# LC_BigOne_-_Comm_Connectors.net
KiCad netlist of a schematic drawn in Altium Designer
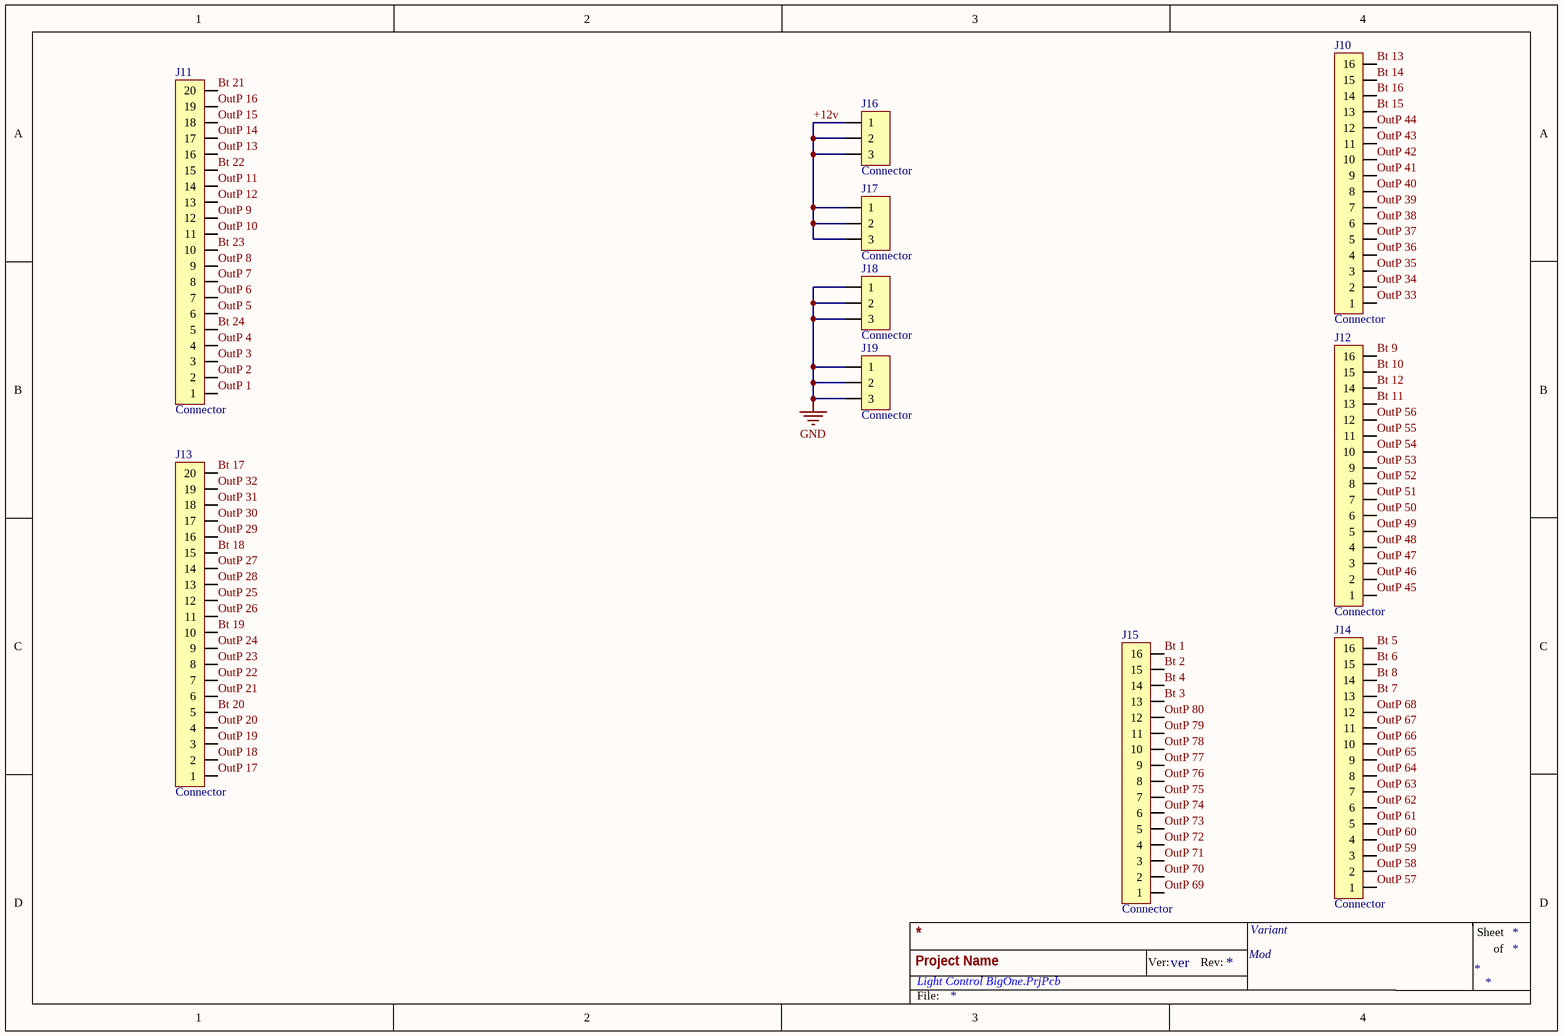
[diagram p0: LC BigOne - Comm Connectors.SchDoc]

(export (version "E")
  (design (tool "Eeschema 10.0.6"))
  (components
    (comp (ref "J10")
      (value "Connector")
      (footprint "Connector:LINE 2.54 x 16D (2 x 8) BH")
      (description "Vert, Dbl line, Male")
      (libsource (lib "Connector") (part "PLD-16 (2 x 8)"))
    )
    (comp (ref "J11")
      (value "Connector")
      (footprint "Connector:LINE 2.54 x 20D (2 x 10) - BH")
      (description "Vert, Dbl line, Male")
      (libsource (lib "Connector") (part "PLD-20 (2 x 10)"))
    )
    (comp (ref "J12")
      (value "Connector")
      (footprint "Connector:LINE 2.54 x 16D (2 x 8) BH")
      (description "Vert, Dbl line, Male")
      (libsource (lib "Connector") (part "PLD-16 (2 x 8)"))
    )
    (comp (ref "J13")
      (value "Connector")
      (footprint "Connector:LINE 2.54 x 20D (2 x 10) - BH")
      (description "Vert, Dbl line, Male")
      (libsource (lib "Connector") (part "PLD-20 (2 x 10)"))
    )
    (comp (ref "J14")
      (value "Connector")
      (footprint "Connector:LINE 2.54 x 16D (2 x 8) BH")
      (description "Vert, Dbl line, Male")
      (libsource (lib "Connector") (part "PLD-16 (2 x 8)"))
    )
    (comp (ref "J15")
      (value "Connector")
      (footprint "Connector:LINE 2.54 x 16D (2 x 8) BH")
      (description "Vert, Dbl line, Male")
      (libsource (lib "Connector") (part "PLD-16 (2 x 8)"))
    )
    (comp (ref "J16")
      (value "Connector")
      (footprint "Connector:DG301 5mm 3p")
      (description "DG301 series")
      (libsource (lib "Connector") (part "DG301-5.0-3P12"))
    )
    (comp (ref "J17")
      (value "Connector")
      (footprint "Connector:DG301 5mm 3p")
      (description "DG301 series")
      (libsource (lib "Connector") (part "DG301-5.0-3P12"))
    )
    (comp (ref "J18")
      (value "Connector")
      (footprint "Connector:DG301 5mm 3p")
      (description "DG301 series")
      (libsource (lib "Connector") (part "DG301-5.0-3P12"))
    )
    (comp (ref "J19")
      (value "Connector")
      (footprint "Connector:DG301 5mm 3p")
      (description "DG301 series")
      (libsource (lib "Connector") (part "DG301-5.0-3P12"))
    )
  )
  (nets
    (net (code "1") (name "/+12v") (class "Default")
      (node (ref "J16") (pin "1") (pinfunction "1_1") (pintype "passive"))
      (node (ref "J16") (pin "2") (pinfunction "2_2") (pintype "passive"))
      (node (ref "J16") (pin "3") (pinfunction "3_3") (pintype "passive"))
      (node (ref "J17") (pin "1") (pinfunction "1_1") (pintype "passive"))
      (node (ref "J17") (pin "2") (pinfunction "2_2") (pintype "passive"))
      (node (ref "J17") (pin "3") (pinfunction "3_3") (pintype "passive"))
    )
    (net (code "2") (name "/Bt 1") (class "Default")
      (node (ref "J15") (pin "16") (pinfunction "16_16") (pintype "passive"))
    )
    (net (code "3") (name "/Bt 2") (class "Default")
      (node (ref "J15") (pin "15") (pinfunction "15_15") (pintype "passive"))
    )
    (net (code "4") (name "/Bt 3") (class "Default")
      (node (ref "J15") (pin "13") (pinfunction "13_13") (pintype "passive"))
    )
    (net (code "5") (name "/Bt 4") (class "Default")
      (node (ref "J15") (pin "14") (pinfunction "14_14") (pintype "passive"))
    )
    (net (code "6") (name "/Bt 5") (class "Default")
      (node (ref "J14") (pin "16") (pinfunction "16_16") (pintype "passive"))
    )
    (net (code "7") (name "/Bt 6") (class "Default")
      (node (ref "J14") (pin "15") (pinfunction "15_15") (pintype "passive"))
    )
    (net (code "8") (name "/Bt 7") (class "Default")
      (node (ref "J14") (pin "13") (pinfunction "13_13") (pintype "passive"))
    )
    (net (code "9") (name "/Bt 8") (class "Default")
      (node (ref "J14") (pin "14") (pinfunction "14_14") (pintype "passive"))
    )
    (net (code "10") (name "/Bt 9") (class "Default")
      (node (ref "J12") (pin "16") (pinfunction "16_16") (pintype "passive"))
    )
    (net (code "11") (name "/Bt 10") (class "Default")
      (node (ref "J12") (pin "15") (pinfunction "15_15") (pintype "passive"))
    )
    (net (code "12") (name "/Bt 11") (class "Default")
      (node (ref "J12") (pin "13") (pinfunction "13_13") (pintype "passive"))
    )
    (net (code "13") (name "/Bt 12") (class "Default")
      (node (ref "J12") (pin "14") (pinfunction "14_14") (pintype "passive"))
    )
    (net (code "14") (name "/Bt 13") (class "Default")
      (node (ref "J10") (pin "16") (pinfunction "16_16") (pintype "passive"))
    )
    (net (code "15") (name "/Bt 14") (class "Default")
      (node (ref "J10") (pin "15") (pinfunction "15_15") (pintype "passive"))
    )
    (net (code "16") (name "/Bt 15") (class "Default")
      (node (ref "J10") (pin "13") (pinfunction "13_13") (pintype "passive"))
    )
    (net (code "17") (name "/Bt 16") (class "Default")
      (node (ref "J10") (pin "14") (pinfunction "14_14") (pintype "passive"))
    )
    (net (code "18") (name "/Bt 17") (class "Default")
      (node (ref "J13") (pin "20") (pinfunction "20_20") (pintype "passive"))
    )
    (net (code "19") (name "/Bt 18") (class "Default")
      (node (ref "J13") (pin "15") (pinfunction "15_15") (pintype "passive"))
    )
    (net (code "20") (name "/Bt 19") (class "Default")
      (node (ref "J13") (pin "10") (pinfunction "10_10") (pintype "passive"))
    )
    (net (code "21") (name "/Bt 20") (class "Default")
      (node (ref "J13") (pin "5") (pinfunction "5_5") (pintype "passive"))
    )
    (net (code "22") (name "/Bt 21") (class "Default")
      (node (ref "J11") (pin "20") (pinfunction "20_20") (pintype "passive"))
    )
    (net (code "23") (name "/Bt 22") (class "Default")
      (node (ref "J11") (pin "15") (pinfunction "15_15") (pintype "passive"))
    )
    (net (code "24") (name "/Bt 23") (class "Default")
      (node (ref "J11") (pin "10") (pinfunction "10_10") (pintype "passive"))
    )
    (net (code "25") (name "/Bt 24") (class "Default")
      (node (ref "J11") (pin "5") (pinfunction "5_5") (pintype "passive"))
    )
    (net (code "26") (name "/OutP 1") (class "Default")
      (node (ref "J11") (pin "1") (pinfunction "1_1") (pintype "passive"))
    )
    (net (code "27") (name "/OutP 2") (class "Default")
      (node (ref "J11") (pin "2") (pinfunction "2_2") (pintype "passive"))
    )
    (net (code "28") (name "/OutP 3") (class "Default")
      (node (ref "J11") (pin "3") (pinfunction "3_3") (pintype "passive"))
    )
    (net (code "29") (name "/OutP 4") (class "Default")
      (node (ref "J11") (pin "4") (pinfunction "4_4") (pintype "passive"))
    )
    (net (code "30") (name "/OutP 5") (class "Default")
      (node (ref "J11") (pin "6") (pinfunction "6_6") (pintype "passive"))
    )
    (net (code "31") (name "/OutP 6") (class "Default")
      (node (ref "J11") (pin "7") (pinfunction "7_7") (pintype "passive"))
    )
    (net (code "32") (name "/OutP 7") (class "Default")
      (node (ref "J11") (pin "8") (pinfunction "8_8") (pintype "passive"))
    )
    (net (code "33") (name "/OutP 8") (class "Default")
      (node (ref "J11") (pin "9") (pinfunction "9_9") (pintype "passive"))
    )
    (net (code "34") (name "/OutP 9") (class "Default")
      (node (ref "J11") (pin "12") (pinfunction "12_12") (pintype "passive"))
    )
    (net (code "35") (name "/OutP 10") (class "Default")
      (node (ref "J11") (pin "11") (pinfunction "11_11") (pintype "passive"))
    )
    (net (code "36") (name "/OutP 11") (class "Default")
      (node (ref "J11") (pin "14") (pinfunction "14_14") (pintype "passive"))
    )
    (net (code "37") (name "/OutP 12") (class "Default")
      (node (ref "J11") (pin "13") (pinfunction "13_13") (pintype "passive"))
    )
    (net (code "38") (name "/OutP 13") (class "Default")
      (node (ref "J11") (pin "16") (pinfunction "16_16") (pintype "passive"))
    )
    (net (code "39") (name "/OutP 14") (class "Default")
      (node (ref "J11") (pin "17") (pinfunction "17_17") (pintype "passive"))
    )
    (net (code "40") (name "/OutP 15") (class "Default")
      (node (ref "J11") (pin "18") (pinfunction "18_18") (pintype "passive"))
    )
    (net (code "41") (name "/OutP 16") (class "Default")
      (node (ref "J11") (pin "19") (pinfunction "19_19") (pintype "passive"))
    )
    (net (code "42") (name "/OutP 17") (class "Default")
      (node (ref "J13") (pin "1") (pinfunction "1_1") (pintype "passive"))
    )
    (net (code "43") (name "/OutP 18") (class "Default")
      (node (ref "J13") (pin "2") (pinfunction "2_2") (pintype "passive"))
    )
    (net (code "44") (name "/OutP 19") (class "Default")
      (node (ref "J13") (pin "3") (pinfunction "3_3") (pintype "passive"))
    )
    (net (code "45") (name "/OutP 20") (class "Default")
      (node (ref "J13") (pin "4") (pinfunction "4_4") (pintype "passive"))
    )
    (net (code "46") (name "/OutP 21") (class "Default")
      (node (ref "J13") (pin "6") (pinfunction "6_6") (pintype "passive"))
    )
    (net (code "47") (name "/OutP 22") (class "Default")
      (node (ref "J13") (pin "7") (pinfunction "7_7") (pintype "passive"))
    )
    (net (code "48") (name "/OutP 23") (class "Default")
      (node (ref "J13") (pin "8") (pinfunction "8_8") (pintype "passive"))
    )
    (net (code "49") (name "/OutP 24") (class "Default")
      (node (ref "J13") (pin "9") (pinfunction "9_9") (pintype "passive"))
    )
    (net (code "50") (name "/OutP 25") (class "Default")
      (node (ref "J13") (pin "12") (pinfunction "12_12") (pintype "passive"))
    )
    (net (code "51") (name "/OutP 26") (class "Default")
      (node (ref "J13") (pin "11") (pinfunction "11_11") (pintype "passive"))
    )
    (net (code "52") (name "/OutP 27") (class "Default")
      (node (ref "J13") (pin "14") (pinfunction "14_14") (pintype "passive"))
    )
    (net (code "53") (name "/OutP 28") (class "Default")
      (node (ref "J13") (pin "13") (pinfunction "13_13") (pintype "passive"))
    )
    (net (code "54") (name "/OutP 29") (class "Default")
      (node (ref "J13") (pin "16") (pinfunction "16_16") (pintype "passive"))
    )
    (net (code "55") (name "/OutP 30") (class "Default")
      (node (ref "J13") (pin "17") (pinfunction "17_17") (pintype "passive"))
    )
    (net (code "56") (name "/OutP 31") (class "Default")
      (node (ref "J13") (pin "18") (pinfunction "18_18") (pintype "passive"))
    )
    (net (code "57") (name "/OutP 32") (class "Default")
      (node (ref "J13") (pin "19") (pinfunction "19_19") (pintype "passive"))
    )
    (net (code "58") (name "/OutP 33") (class "Default")
      (node (ref "J10") (pin "1") (pinfunction "1_1") (pintype "passive"))
    )
    (net (code "59") (name "/OutP 34") (class "Default")
      (node (ref "J10") (pin "2") (pinfunction "2_2") (pintype "passive"))
    )
    (net (code "60") (name "/OutP 35") (class "Default")
      (node (ref "J10") (pin "3") (pinfunction "3_3") (pintype "passive"))
    )
    (net (code "61") (name "/OutP 36") (class "Default")
      (node (ref "J10") (pin "4") (pinfunction "4_4") (pintype "passive"))
    )
    (net (code "62") (name "/OutP 37") (class "Default")
      (node (ref "J10") (pin "5") (pinfunction "5_5") (pintype "passive"))
    )
    (net (code "63") (name "/OutP 38") (class "Default")
      (node (ref "J10") (pin "6") (pinfunction "6_6") (pintype "passive"))
    )
    (net (code "64") (name "/OutP 39") (class "Default")
      (node (ref "J10") (pin "7") (pinfunction "7_7") (pintype "passive"))
    )
    (net (code "65") (name "/OutP 40") (class "Default")
      (node (ref "J10") (pin "8") (pinfunction "8_8") (pintype "passive"))
    )
    (net (code "66") (name "/OutP 41") (class "Default")
      (node (ref "J10") (pin "9") (pinfunction "9_9") (pintype "passive"))
    )
    (net (code "67") (name "/OutP 42") (class "Default")
      (node (ref "J10") (pin "10") (pinfunction "10_10") (pintype "passive"))
    )
    (net (code "68") (name "/OutP 43") (class "Default")
      (node (ref "J10") (pin "11") (pinfunction "11_11") (pintype "passive"))
    )
    (net (code "69") (name "/OutP 44") (class "Default")
      (node (ref "J10") (pin "12") (pinfunction "12_12") (pintype "passive"))
    )
    (net (code "70") (name "/OutP 45") (class "Default")
      (node (ref "J12") (pin "1") (pinfunction "1_1") (pintype "passive"))
    )
    (net (code "71") (name "/OutP 46") (class "Default")
      (node (ref "J12") (pin "2") (pinfunction "2_2") (pintype "passive"))
    )
    (net (code "72") (name "/OutP 47") (class "Default")
      (node (ref "J12") (pin "3") (pinfunction "3_3") (pintype "passive"))
    )
    (net (code "73") (name "/OutP 48") (class "Default")
      (node (ref "J12") (pin "4") (pinfunction "4_4") (pintype "passive"))
    )
    (net (code "74") (name "/OutP 49") (class "Default")
      (node (ref "J12") (pin "5") (pinfunction "5_5") (pintype "passive"))
    )
    (net (code "75") (name "/OutP 50") (class "Default")
      (node (ref "J12") (pin "6") (pinfunction "6_6") (pintype "passive"))
    )
    (net (code "76") (name "/OutP 51") (class "Default")
      (node (ref "J12") (pin "7") (pinfunction "7_7") (pintype "passive"))
    )
    (net (code "77") (name "/OutP 52") (class "Default")
      (node (ref "J12") (pin "8") (pinfunction "8_8") (pintype "passive"))
    )
    (net (code "78") (name "/OutP 53") (class "Default")
      (node (ref "J12") (pin "9") (pinfunction "9_9") (pintype "passive"))
    )
    (net (code "79") (name "/OutP 54") (class "Default")
      (node (ref "J12") (pin "10") (pinfunction "10_10") (pintype "passive"))
    )
    (net (code "80") (name "/OutP 55") (class "Default")
      (node (ref "J12") (pin "11") (pinfunction "11_11") (pintype "passive"))
    )
    (net (code "81") (name "/OutP 56") (class "Default")
      (node (ref "J12") (pin "12") (pinfunction "12_12") (pintype "passive"))
    )
    (net (code "82") (name "/OutP 57") (class "Default")
      (node (ref "J14") (pin "1") (pinfunction "1_1") (pintype "passive"))
    )
    (net (code "83") (name "/OutP 58") (class "Default")
      (node (ref "J14") (pin "2") (pinfunction "2_2") (pintype "passive"))
    )
    (net (code "84") (name "/OutP 59") (class "Default")
      (node (ref "J14") (pin "3") (pinfunction "3_3") (pintype "passive"))
    )
    (net (code "85") (name "/OutP 60") (class "Default")
      (node (ref "J14") (pin "4") (pinfunction "4_4") (pintype "passive"))
    )
    (net (code "86") (name "/OutP 61") (class "Default")
      (node (ref "J14") (pin "5") (pinfunction "5_5") (pintype "passive"))
    )
    (net (code "87") (name "/OutP 62") (class "Default")
      (node (ref "J14") (pin "6") (pinfunction "6_6") (pintype "passive"))
    )
    (net (code "88") (name "/OutP 63") (class "Default")
      (node (ref "J14") (pin "7") (pinfunction "7_7") (pintype "passive"))
    )
    (net (code "89") (name "/OutP 64") (class "Default")
      (node (ref "J14") (pin "8") (pinfunction "8_8") (pintype "passive"))
    )
    (net (code "90") (name "/OutP 65") (class "Default")
      (node (ref "J14") (pin "9") (pinfunction "9_9") (pintype "passive"))
    )
    (net (code "91") (name "/OutP 66") (class "Default")
      (node (ref "J14") (pin "10") (pinfunction "10_10") (pintype "passive"))
    )
    (net (code "92") (name "/OutP 67") (class "Default")
      (node (ref "J14") (pin "11") (pinfunction "11_11") (pintype "passive"))
    )
    (net (code "93") (name "/OutP 68") (class "Default")
      (node (ref "J14") (pin "12") (pinfunction "12_12") (pintype "passive"))
    )
    (net (code "94") (name "/OutP 69") (class "Default")
      (node (ref "J15") (pin "1") (pinfunction "1_1") (pintype "passive"))
    )
    (net (code "95") (name "/OutP 70") (class "Default")
      (node (ref "J15") (pin "2") (pinfunction "2_2") (pintype "passive"))
    )
    (net (code "96") (name "/OutP 71") (class "Default")
      (node (ref "J15") (pin "3") (pinfunction "3_3") (pintype "passive"))
    )
    (net (code "97") (name "/OutP 72") (class "Default")
      (node (ref "J15") (pin "4") (pinfunction "4_4") (pintype "passive"))
    )
    (net (code "98") (name "/OutP 73") (class "Default")
      (node (ref "J15") (pin "5") (pinfunction "5_5") (pintype "passive"))
    )
    (net (code "99") (name "/OutP 74") (class "Default")
      (node (ref "J15") (pin "6") (pinfunction "6_6") (pintype "passive"))
    )
    (net (code "100") (name "/OutP 75") (class "Default")
      (node (ref "J15") (pin "7") (pinfunction "7_7") (pintype "passive"))
    )
    (net (code "101") (name "/OutP 76") (class "Default")
      (node (ref "J15") (pin "8") (pinfunction "8_8") (pintype "passive"))
    )
    (net (code "102") (name "/OutP 77") (class "Default")
      (node (ref "J15") (pin "9") (pinfunction "9_9") (pintype "passive"))
    )
    (net (code "103") (name "/OutP 78") (class "Default")
      (node (ref "J15") (pin "10") (pinfunction "10_10") (pintype "passive"))
    )
    (net (code "104") (name "/OutP 79") (class "Default")
      (node (ref "J15") (pin "11") (pinfunction "11_11") (pintype "passive"))
    )
    (net (code "105") (name "/OutP 80") (class "Default")
      (node (ref "J15") (pin "12") (pinfunction "12_12") (pintype "passive"))
    )
    (net (code "106") (name "GND") (class "Default")
      (node (ref "J18") (pin "1") (pinfunction "1_1") (pintype "passive"))
      (node (ref "J18") (pin "2") (pinfunction "2_2") (pintype "passive"))
      (node (ref "J18") (pin "3") (pinfunction "3_3") (pintype "passive"))
      (node (ref "J19") (pin "1") (pinfunction "1_1") (pintype "passive"))
      (node (ref "J19") (pin "2") (pinfunction "2_2") (pintype "passive"))
      (node (ref "J19") (pin "3") (pinfunction "3_3") (pintype "passive"))
    )
  )
)
